# 04-Energy-Harvester.net
KiCad netlist of a schematic drawn in Altium Designer
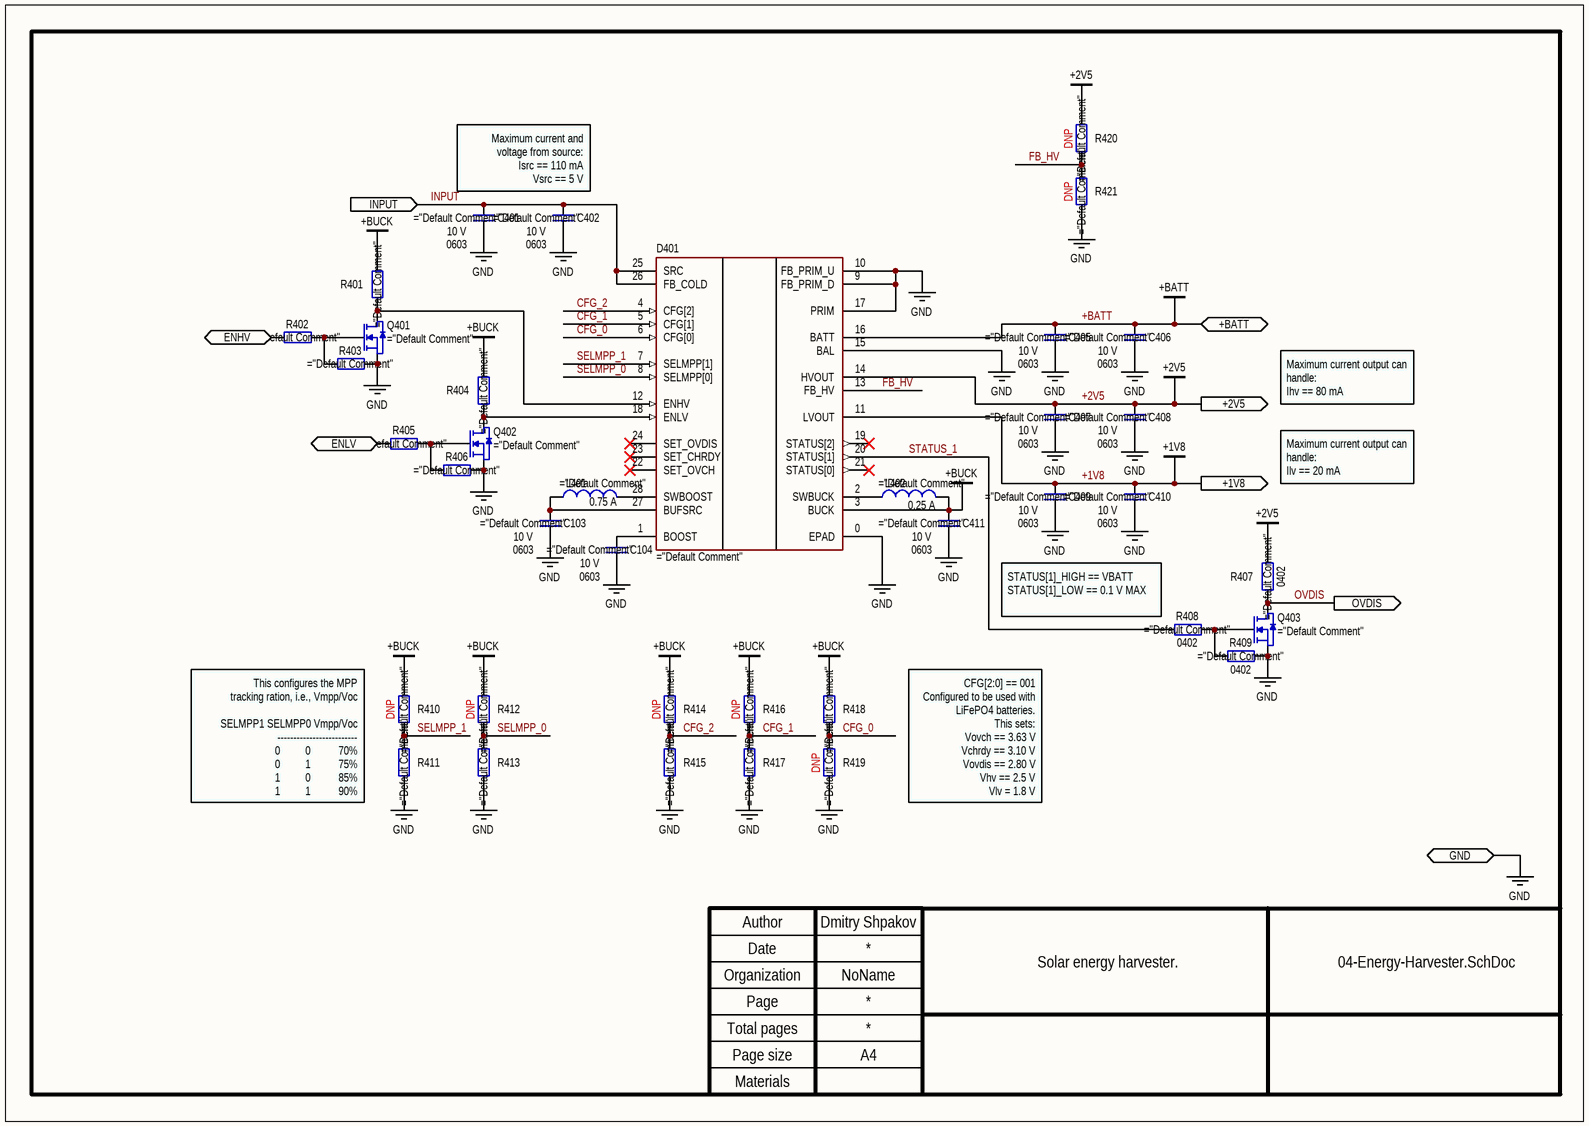
[diagram p0: 04-Energy-Harvester.SchDoc]

(export (version "E")
  (design (tool "Eeschema 10.0.6"))
  (components
    (comp (ref "C103")
      (value "~")
      (footprint "CAP0603HD")
      (description "CAP CER 10UF 10V X5R 0603")
      (fields
        (field (name "MANUFACTURER") "Murata Electronics")
        (field (name "TOLERANCE") "20 %")
        (field (name "RATED VOLTAGE") "10 V")
        (field (name "CASE") "0603")
      )
      (libsource (lib "Capacitors") (part "GRM188R61A106ME69D"))
    )
    (comp (ref "C104")
      (value "~")
      (footprint "CAP0603HD")
      (description "CAP CER 22UF 10V X5R 0603")
      (fields
        (field (name "MANUFACTURER") "Murata Electronics")
        (field (name "TOLERANCE") "20 %")
        (field (name "CASE") "0603")
        (field (name "RATED VOLTAGE") "10 V")
      )
      (libsource (lib "Capacitors") (part "GRM188R61A226ME15J"))
    )
    (comp (ref "C401")
      (value "~")
      (footprint "CAP0603HD")
      (description "CAP CER 22UF 10V X5R 0603")
      (fields
        (field (name "MANUFACTURER") "Murata Electronics")
        (field (name "TOLERANCE") "20 %")
        (field (name "CASE") "0603")
        (field (name "RATED VOLTAGE") "10 V")
      )
      (libsource (lib "Capacitors") (part "GRM188R61A226ME15J"))
    )
    (comp (ref "C402")
      (value "~")
      (footprint "CAP0603HD")
      (description "CAP CER 10UF 10V X5R 0603")
      (fields
        (field (name "MANUFACTURER") "Murata Electronics")
        (field (name "TOLERANCE") "20 %")
        (field (name "RATED VOLTAGE") "10 V")
        (field (name "CASE") "0603")
      )
      (libsource (lib "Capacitors") (part "GRM188R61A106ME69D"))
    )
    (comp (ref "C405")
      (value "~")
      (footprint "CAP0603HD")
      (description "CAP CER 22UF 10V X5R 0603")
      (fields
        (field (name "MANUFACTURER") "Murata Electronics")
        (field (name "TOLERANCE") "20 %")
        (field (name "CASE") "0603")
        (field (name "RATED VOLTAGE") "10 V")
      )
      (libsource (lib "Capacitors") (part "GRM188R61A226ME15J"))
    )
    (comp (ref "C406")
      (value "~")
      (footprint "CAP0603HD")
      (description "CAP CER 10UF 10V X5R 0603")
      (fields
        (field (name "MANUFACTURER") "Murata Electronics")
        (field (name "TOLERANCE") "20 %")
        (field (name "RATED VOLTAGE") "10 V")
        (field (name "CASE") "0603")
      )
      (libsource (lib "Capacitors") (part "GRM188R61A106ME69D"))
    )
    (comp (ref "C407")
      (value "~")
      (footprint "CAP0603HD")
      (description "CAP CER 22UF 10V X5R 0603")
      (fields
        (field (name "MANUFACTURER") "Murata Electronics")
        (field (name "TOLERANCE") "20 %")
        (field (name "CASE") "0603")
        (field (name "RATED VOLTAGE") "10 V")
      )
      (libsource (lib "Capacitors") (part "GRM188R61A226ME15J"))
    )
    (comp (ref "C408")
      (value "~")
      (footprint "CAP0603HD")
      (description "CAP CER 10UF 10V X5R 0603")
      (fields
        (field (name "MANUFACTURER") "Murata Electronics")
        (field (name "TOLERANCE") "20 %")
        (field (name "RATED VOLTAGE") "10 V")
        (field (name "CASE") "0603")
      )
      (libsource (lib "Capacitors") (part "GRM188R61A106ME69D"))
    )
    (comp (ref "C409")
      (value "~")
      (footprint "CAP0603HD")
      (description "CAP CER 22UF 10V X5R 0603")
      (fields
        (field (name "MANUFACTURER") "Murata Electronics")
        (field (name "TOLERANCE") "20 %")
        (field (name "CASE") "0603")
        (field (name "RATED VOLTAGE") "10 V")
      )
      (libsource (lib "Capacitors") (part "GRM188R61A226ME15J"))
    )
    (comp (ref "C410")
      (value "~")
      (footprint "CAP0603HD")
      (description "CAP CER 10UF 10V X5R 0603")
      (fields
        (field (name "MANUFACTURER") "Murata Electronics")
        (field (name "TOLERANCE") "20 %")
        (field (name "RATED VOLTAGE") "10 V")
        (field (name "CASE") "0603")
      )
      (libsource (lib "Capacitors") (part "GRM188R61A106ME69D"))
    )
    (comp (ref "C411")
      (value "~")
      (footprint "CAP0603HD")
      (description "CAP CER 10UF 10V X5R 0603")
      (fields
        (field (name "MANUFACTURER") "Murata Electronics")
        (field (name "TOLERANCE") "20 %")
        (field (name "RATED VOLTAGE") "10 V")
        (field (name "CASE") "0603")
      )
      (libsource (lib "Capacitors") (part "GRM188R61A106ME69D"))
    )
    (comp (ref "D401")
      (value "~")
      (footprint "AEM10941-QFN28")
      (description "Power Management Specialised - PMIC AEM10941 IC - Photovoltaic Energy Harvesting Manager")
      (fields (field (name "MANUFACTURER") "e-peas") (field (name "TOLERANCE") "* %"))
      (libsource (lib "ICs") (part "AEM10941"))
    )
    (comp (ref "L401")
      (value "~")
      (footprint "LPS4012-103MRC")
      (description "Fixed Inductors 10uH Shld 20% 1.1A 350 mOhms")
      (fields
        (field (name "MANUFACTURER") "Coilcraft")
        (field (name "TOLERANCE") "20 %")
        (field (name "RATED CURRENT") "0.75 A")
      )
      (libsource (lib "Inductors") (part "LPS4012-103MRC"))
    )
    (comp (ref "L402")
      (value "~")
      (footprint "MLZ1608M100WTD25")
      (description "FIXED IND 10UH 250MA 1.05OHM SMD")
      (fields
        (field (name "MANUFACTURER") "TDK Corporation")
        (field (name "TOLERANCE") "20 %")
        (field (name "RATED CURRENT") "0.25 A")
      )
      (libsource (lib "Inductors") (part "MLZ1608M100WTD25"))
    )
    (comp (ref "Q401")
      (value "~")
      (footprint "DMG1012UW-7")
      (description "MOSFET N-CH 20V 1A SOT323")
      (fields (field (name "MANUFACTURER") "Diodes Incorporated") (field (name "TOLERANCE") "* %"))
      (libsource (lib "Transistors") (part "DMG1012UW-7"))
    )
    (comp (ref "Q402")
      (value "~")
      (footprint "DMG1012UW-7")
      (description "MOSFET N-CH 20V 1A SOT323")
      (fields (field (name "MANUFACTURER") "Diodes Incorporated") (field (name "TOLERANCE") "* %"))
      (libsource (lib "Transistors") (part "DMG1012UW-7"))
    )
    (comp (ref "Q403")
      (value "~")
      (footprint "DMG1012UW-7")
      (description "MOSFET N-CH 20V 1A SOT323")
      (fields (field (name "MANUFACTURER") "Diodes Incorporated") (field (name "TOLERANCE") "* %"))
      (libsource (lib "Transistors") (part "DMG1012UW-7"))
    )
    (comp (ref "R401")
      (value "~")
      (footprint "0402")
      (description "RES 10K OHM 5% 1/16W 0402")
      (fields (field (name "MANUFACTURER") "YAGEO") (field (name "TOLERANCE") "5 %"))
      (libsource (lib "Resistors") (part "RC0402JR-0710KL"))
    )
    (comp (ref "R402")
      (value "~")
      (footprint "0402")
      (description "RES 100 OHM 1% 1/16W 0402")
      (fields (field (name "MANUFACTURER") "YAGEO") (field (name "TOLERANCE") "1 %"))
      (libsource (lib "Resistors") (part "RC0402FR-07100RL"))
    )
    (comp (ref "R403")
      (value "~")
      (footprint "0402")
      (description "RES 10K OHM 5% 1/16W 0402")
      (fields (field (name "MANUFACTURER") "YAGEO") (field (name "TOLERANCE") "5 %"))
      (libsource (lib "Resistors") (part "RC0402JR-0710KL"))
    )
    (comp (ref "R404")
      (value "~")
      (footprint "0402")
      (description "RES 10K OHM 5% 1/16W 0402")
      (fields (field (name "MANUFACTURER") "YAGEO") (field (name "TOLERANCE") "5 %"))
      (libsource (lib "Resistors") (part "RC0402JR-0710KL"))
    )
    (comp (ref "R405")
      (value "~")
      (footprint "0402")
      (description "RES 100 OHM 1% 1/16W 0402")
      (fields (field (name "MANUFACTURER") "YAGEO") (field (name "TOLERANCE") "1 %"))
      (libsource (lib "Resistors") (part "RC0402FR-07100RL"))
    )
    (comp (ref "R406")
      (value "~")
      (footprint "0402")
      (description "RES 10K OHM 5% 1/16W 0402")
      (fields (field (name "MANUFACTURER") "YAGEO") (field (name "TOLERANCE") "5 %"))
      (libsource (lib "Resistors") (part "RC0402JR-0710KL"))
    )
    (comp (ref "R407")
      (value "~")
      (footprint "0402")
      (description "RES 10K OHM 5% 1/16W 0402")
      (fields
        (field (name "MANUFACTURER") "YAGEO")
        (field (name "TOLERANCE") "5 %")
        (field (name "CASE") "0402")
      )
      (libsource (lib "Resistors") (part "RC0402JR-0710KL"))
    )
    (comp (ref "R408")
      (value "~")
      (footprint "0402")
      (description "RES 100 OHM 1% 1/16W 0402")
      (fields
        (field (name "MANUFACTURER") "YAGEO")
        (field (name "TOLERANCE") "1 %")
        (field (name "CASE") "0402")
      )
      (libsource (lib "Resistors") (part "RC0402FR-07100RL"))
    )
    (comp (ref "R409")
      (value "~")
      (footprint "0402")
      (description "RES 10K OHM 5% 1/16W 0402")
      (fields
        (field (name "MANUFACTURER") "YAGEO")
        (field (name "TOLERANCE") "5 %")
        (field (name "CASE") "0402")
      )
      (libsource (lib "Resistors") (part "RC0402JR-0710KL"))
    )
    (comp (ref "R410")
      (value "~")
      (footprint "0402")
      (description "RES 0 OHM JUMPER 1/16W 0402")
      (fields
        (field (name "MANUFACTURER") "YAGEO")
        (field (name "TOLERANCE") "jumper")
        (field (name "ASSEMBLY") "DNP")
      )
      (libsource (lib "Resistors") (part "RC0402FR-070RL"))
    )
    (comp (ref "R411")
      (value "~")
      (footprint "0402")
      (description "RES 0 OHM JUMPER 1/16W 0402")
      (fields (field (name "MANUFACTURER") "YAGEO") (field (name "TOLERANCE") "jumper"))
      (libsource (lib "Resistors") (part "RC0402FR-070RL"))
    )
    (comp (ref "R412")
      (value "~")
      (footprint "0402")
      (description "RES 0 OHM JUMPER 1/16W 0402")
      (fields
        (field (name "MANUFACTURER") "YAGEO")
        (field (name "TOLERANCE") "jumper")
        (field (name "ASSEMBLY") "DNP")
      )
      (libsource (lib "Resistors") (part "RC0402FR-070RL"))
    )
    (comp (ref "R413")
      (value "~")
      (footprint "0402")
      (description "RES 0 OHM JUMPER 1/16W 0402")
      (fields (field (name "MANUFACTURER") "YAGEO") (field (name "TOLERANCE") "jumper"))
      (libsource (lib "Resistors") (part "RC0402FR-070RL"))
    )
    (comp (ref "R414")
      (value "~")
      (footprint "0402")
      (description "RES 0 OHM JUMPER 1/16W 0402")
      (fields
        (field (name "MANUFACTURER") "YAGEO")
        (field (name "TOLERANCE") "jumper")
        (field (name "ASSEMBLY") "DNP")
      )
      (libsource (lib "Resistors") (part "RC0402FR-070RL"))
    )
    (comp (ref "R415")
      (value "~")
      (footprint "0402")
      (description "RES 0 OHM JUMPER 1/16W 0402")
      (fields (field (name "MANUFACTURER") "YAGEO") (field (name "TOLERANCE") "jumper"))
      (libsource (lib "Resistors") (part "RC0402FR-070RL"))
    )
    (comp (ref "R416")
      (value "~")
      (footprint "0402")
      (description "RES 0 OHM JUMPER 1/16W 0402")
      (fields
        (field (name "MANUFACTURER") "YAGEO")
        (field (name "TOLERANCE") "jumper")
        (field (name "ASSEMBLY") "DNP")
      )
      (libsource (lib "Resistors") (part "RC0402FR-070RL"))
    )
    (comp (ref "R417")
      (value "~")
      (footprint "0402")
      (description "RES 0 OHM JUMPER 1/16W 0402")
      (fields (field (name "MANUFACTURER") "YAGEO") (field (name "TOLERANCE") "jumper"))
      (libsource (lib "Resistors") (part "RC0402FR-070RL"))
    )
    (comp (ref "R418")
      (value "~")
      (footprint "0402")
      (description "RES 0 OHM JUMPER 1/16W 0402")
      (fields (field (name "MANUFACTURER") "YAGEO") (field (name "TOLERANCE") "jumper"))
      (libsource (lib "Resistors") (part "RC0402FR-070RL"))
    )
    (comp (ref "R419")
      (value "~")
      (footprint "0402")
      (description "RES 0 OHM JUMPER 1/16W 0402")
      (fields
        (field (name "MANUFACTURER") "YAGEO")
        (field (name "TOLERANCE") "jumper")
        (field (name "ASSEMBLY") "DNP")
      )
      (libsource (lib "Resistors") (part "RC0402FR-070RL"))
    )
    (comp (ref "R420")
      (value "~")
      (footprint "0402")
      (description "RES 0 OHM JUMPER 1/16W 0402")
      (fields
        (field (name "MANUFACTURER") "YAGEO")
        (field (name "TOLERANCE") "jumper")
        (field (name "ASSEMBLY") "DNP")
      )
      (libsource (lib "Resistors") (part "RC0402FR-070RL"))
    )
    (comp (ref "R421")
      (value "~")
      (footprint "0402")
      (description "RES 0 OHM JUMPER 1/16W 0402")
      (fields
        (field (name "MANUFACTURER") "YAGEO")
        (field (name "TOLERANCE") "jumper")
        (field (name "ASSEMBLY") "DNP")
      )
      (libsource (lib "Resistors") (part "RC0402FR-070RL"))
    )
  )
  (nets
    (net (code "1") (name "+1V8") (class "Default")
      (node (ref "C409") (pin "2") (pintype "passive"))
      (node (ref "C410") (pin "2") (pintype "passive"))
      (node (ref "D401") (pin "11") (pinfunction "LVOUT_11") (pintype "power_in"))
    )
    (net (code "2") (name "+2V5") (class "Default")
      (node (ref "C407") (pin "2") (pintype "passive"))
      (node (ref "C408") (pin "2") (pintype "passive"))
      (node (ref "D401") (pin "14") (pinfunction "HVOUT_14") (pintype "power_in"))
      (node (ref "R407") (pin "2") (pinfunction "2_2") (pintype "passive"))
      (node (ref "R420") (pin "2") (pinfunction "2_2") (pintype "passive"))
    )
    (net (code "3") (name "+BATT") (class "Default")
      (node (ref "C405") (pin "2") (pintype "passive"))
      (node (ref "C406") (pin "2") (pintype "passive"))
      (node (ref "D401") (pin "16") (pinfunction "BATT_16") (pintype "passive"))
    )
    (net (code "4") (name "+BUCK") (class "Default")
      (node (ref "C411") (pin "2") (pintype "passive"))
      (node (ref "D401") (pin "3") (pinfunction "BUCK_3") (pintype "power_in"))
      (node (ref "L402") (pin "2") (pinfunction "2_2") (pintype "passive"))
      (node (ref "R401") (pin "2") (pinfunction "2_2") (pintype "passive"))
      (node (ref "R404") (pin "2") (pinfunction "2_2") (pintype "passive"))
      (node (ref "R410") (pin "2") (pinfunction "2_2") (pintype "passive"))
      (node (ref "R412") (pin "2") (pinfunction "2_2") (pintype "passive"))
      (node (ref "R414") (pin "2") (pinfunction "2_2") (pintype "passive"))
      (node (ref "R416") (pin "2") (pinfunction "2_2") (pintype "passive"))
      (node (ref "R418") (pin "2") (pinfunction "2_2") (pintype "passive"))
    )
    (net (code "5") (name "/CFG_0") (class "Default")
      (node (ref "D401") (pin "6") (pinfunction "CFG[0]_6") (pintype "input"))
      (node (ref "R418") (pin "1") (pinfunction "1_1") (pintype "passive"))
      (node (ref "R419") (pin "2") (pinfunction "2_2") (pintype "passive"))
    )
    (net (code "6") (name "/CFG_1") (class "Default")
      (node (ref "D401") (pin "5") (pinfunction "CFG[1]_5") (pintype "input"))
      (node (ref "R416") (pin "1") (pinfunction "1_1") (pintype "passive"))
      (node (ref "R417") (pin "2") (pinfunction "2_2") (pintype "passive"))
    )
    (net (code "7") (name "/CFG_2") (class "Default")
      (node (ref "D401") (pin "4") (pinfunction "CFG[2]_4") (pintype "input"))
      (node (ref "R414") (pin "1") (pinfunction "1_1") (pintype "passive"))
      (node (ref "R415") (pin "2") (pinfunction "2_2") (pintype "passive"))
    )
    (net (code "8") (name "/ENHV") (class "Default")
      (node (ref "R402") (pin "1") (pinfunction "1_1") (pintype "passive"))
    )
    (net (code "9") (name "/ENLV") (class "Default")
      (node (ref "R405") (pin "1") (pinfunction "1_1") (pintype "passive"))
    )
    (net (code "10") (name "/FB_HV") (class "Default")
      (node (ref "D401") (pin "13") (pinfunction "FB_HV_13") (pintype "passive"))
      (node (ref "R420") (pin "1") (pinfunction "1_1") (pintype "passive"))
      (node (ref "R421") (pin "2") (pinfunction "2_2") (pintype "passive"))
    )
    (net (code "11") (name "/INPUT") (class "Default")
      (node (ref "C401") (pin "2") (pintype "passive"))
      (node (ref "C402") (pin "2") (pintype "passive"))
      (node (ref "D401") (pin "25") (pinfunction "SRC_25") (pintype "passive"))
      (node (ref "D401") (pin "26") (pinfunction "FB_COLD_26") (pintype "passive"))
    )
    (net (code "12") (name "/OVDIS") (class "Default")
      (node (ref "Q403") (pin "D") (pinfunction "D_D") (pintype "passive"))
      (node (ref "R407") (pin "1") (pinfunction "1_1") (pintype "passive"))
    )
    (net (code "13") (name "/SELMPP_0") (class "Default")
      (node (ref "D401") (pin "8") (pinfunction "SELMPP[0]_8") (pintype "input"))
      (node (ref "R412") (pin "1") (pinfunction "1_1") (pintype "passive"))
      (node (ref "R413") (pin "2") (pinfunction "2_2") (pintype "passive"))
    )
    (net (code "14") (name "/SELMPP_1") (class "Default")
      (node (ref "D401") (pin "7") (pinfunction "SELMPP[1]_7") (pintype "input"))
      (node (ref "R410") (pin "1") (pinfunction "1_1") (pintype "passive"))
      (node (ref "R411") (pin "2") (pinfunction "2_2") (pintype "passive"))
    )
    (net (code "15") (name "/STATUS_1") (class "Default")
      (node (ref "D401") (pin "20") (pinfunction "STATUS[1]_20") (pintype "output"))
      (node (ref "R408") (pin "1") (pinfunction "1_1") (pintype "passive"))
    )
    (net (code "16") (name "GND") (class "Default")
      (node (ref "C103") (pin "1") (pintype "passive"))
      (node (ref "C104") (pin "1") (pintype "passive"))
      (node (ref "C401") (pin "1") (pintype "passive"))
      (node (ref "C402") (pin "1") (pintype "passive"))
      (node (ref "C405") (pin "1") (pintype "passive"))
      (node (ref "C406") (pin "1") (pintype "passive"))
      (node (ref "C407") (pin "1") (pintype "passive"))
      (node (ref "C408") (pin "1") (pintype "passive"))
      (node (ref "C409") (pin "1") (pintype "passive"))
      (node (ref "C410") (pin "1") (pintype "passive"))
      (node (ref "C411") (pin "1") (pintype "passive"))
      (node (ref "D401") (pin "0") (pinfunction "EPAD_0") (pintype "passive"))
      (node (ref "D401") (pin "10") (pinfunction "FB_PRIM_U_10") (pintype "passive"))
      (node (ref "D401") (pin "15") (pinfunction "BAL_15") (pintype "passive"))
      (node (ref "D401") (pin "17") (pinfunction "PRIM_17") (pintype "passive"))
      (node (ref "D401") (pin "9") (pinfunction "FB_PRIM_D_9") (pintype "passive"))
      (node (ref "Q401") (pin "S") (pinfunction "S_S") (pintype "passive"))
      (node (ref "Q402") (pin "S") (pinfunction "S_S") (pintype "passive"))
      (node (ref "Q403") (pin "S") (pinfunction "S_S") (pintype "passive"))
      (node (ref "R403") (pin "2") (pinfunction "2_2") (pintype "passive"))
      (node (ref "R406") (pin "2") (pinfunction "2_2") (pintype "passive"))
      (node (ref "R409") (pin "2") (pinfunction "2_2") (pintype "passive"))
      (node (ref "R411") (pin "1") (pinfunction "1_1") (pintype "passive"))
      (node (ref "R413") (pin "1") (pinfunction "1_1") (pintype "passive"))
      (node (ref "R415") (pin "1") (pinfunction "1_1") (pintype "passive"))
      (node (ref "R417") (pin "1") (pinfunction "1_1") (pintype "passive"))
      (node (ref "R419") (pin "1") (pinfunction "1_1") (pintype "passive"))
      (node (ref "R421") (pin "1") (pinfunction "1_1") (pintype "passive"))
    )
    (net (code "17") (name "Net-(D401-BOOST)") (class "Default")
      (node (ref "C104") (pin "2") (pintype "passive"))
      (node (ref "D401") (pin "1") (pinfunction "BOOST_1") (pintype "passive"))
    )
    (net (code "18") (name "Net-(D401-BUFSRC)") (class "Default")
      (node (ref "C103") (pin "2") (pintype "passive"))
      (node (ref "D401") (pin "27") (pinfunction "BUFSRC_27") (pintype "passive"))
      (node (ref "L401") (pin "1") (pinfunction "1_1") (pintype "passive"))
    )
    (net (code "19") (name "Net-(D401-ENHV)") (class "Default")
      (node (ref "D401") (pin "12") (pinfunction "ENHV_12") (pintype "input"))
      (node (ref "Q401") (pin "D") (pinfunction "D_D") (pintype "passive"))
      (node (ref "R401") (pin "1") (pinfunction "1_1") (pintype "passive"))
    )
    (net (code "20") (name "Net-(D401-ENLV)") (class "Default")
      (node (ref "D401") (pin "18") (pinfunction "ENLV_18") (pintype "input"))
      (node (ref "Q402") (pin "D") (pinfunction "D_D") (pintype "passive"))
      (node (ref "R404") (pin "1") (pinfunction "1_1") (pintype "passive"))
    )
    (net (code "21") (name "Net-(D401-SWBOOST)") (class "Default")
      (node (ref "D401") (pin "28") (pinfunction "SWBOOST_28") (pintype "passive"))
      (node (ref "L401") (pin "2") (pinfunction "2_2") (pintype "passive"))
    )
    (net (code "22") (name "Net-(D401-SWBUCK)") (class "Default")
      (node (ref "D401") (pin "2") (pinfunction "SWBUCK_2") (pintype "passive"))
      (node (ref "L402") (pin "1") (pinfunction "1_1") (pintype "passive"))
    )
    (net (code "23") (name "Net-(Q401-PadG)") (class "Default")
      (node (ref "Q401") (pin "G") (pinfunction "G_G") (pintype "passive"))
      (node (ref "R402") (pin "2") (pinfunction "2_2") (pintype "passive"))
      (node (ref "R403") (pin "1") (pinfunction "1_1") (pintype "passive"))
    )
    (net (code "24") (name "Net-(Q402-PadG)") (class "Default")
      (node (ref "Q402") (pin "G") (pinfunction "G_G") (pintype "passive"))
      (node (ref "R405") (pin "2") (pinfunction "2_2") (pintype "passive"))
      (node (ref "R406") (pin "1") (pinfunction "1_1") (pintype "passive"))
    )
    (net (code "25") (name "Net-(Q403-PadG)") (class "Default")
      (node (ref "Q403") (pin "G") (pinfunction "G_G") (pintype "passive"))
      (node (ref "R408") (pin "2") (pinfunction "2_2") (pintype "passive"))
      (node (ref "R409") (pin "1") (pinfunction "1_1") (pintype "passive"))
    )
    (net (code "26") (name "unconnected-(D401-SET_CHRDY-Pad23)") (class "Default")
      (node (ref "D401") (pin "23") (pinfunction "SET_CHRDY_23") (pintype "passive+no_connect"))
    )
    (net (code "27") (name "unconnected-(D401-SET_OVCH-Pad22)") (class "Default")
      (node (ref "D401") (pin "22") (pinfunction "SET_OVCH_22") (pintype "passive+no_connect"))
    )
    (net (code "28") (name "unconnected-(D401-SET_OVDIS-Pad24)") (class "Default")
      (node (ref "D401") (pin "24") (pinfunction "SET_OVDIS_24") (pintype "passive+no_connect"))
    )
    (net (code "29") (name "unconnected-(D401-STATUS[0]-Pad21)") (class "Default")
      (node (ref "D401") (pin "21") (pinfunction "STATUS[0]_21") (pintype "output+no_connect"))
    )
    (net (code "30") (name "unconnected-(D401-STATUS[2]-Pad19)") (class "Default")
      (node (ref "D401") (pin "19") (pinfunction "STATUS[2]_19") (pintype "output+no_connect"))
    )
  )
)
